# tvac_systems_interface.net
KiCad netlist of a schematic drawn in EAGLE
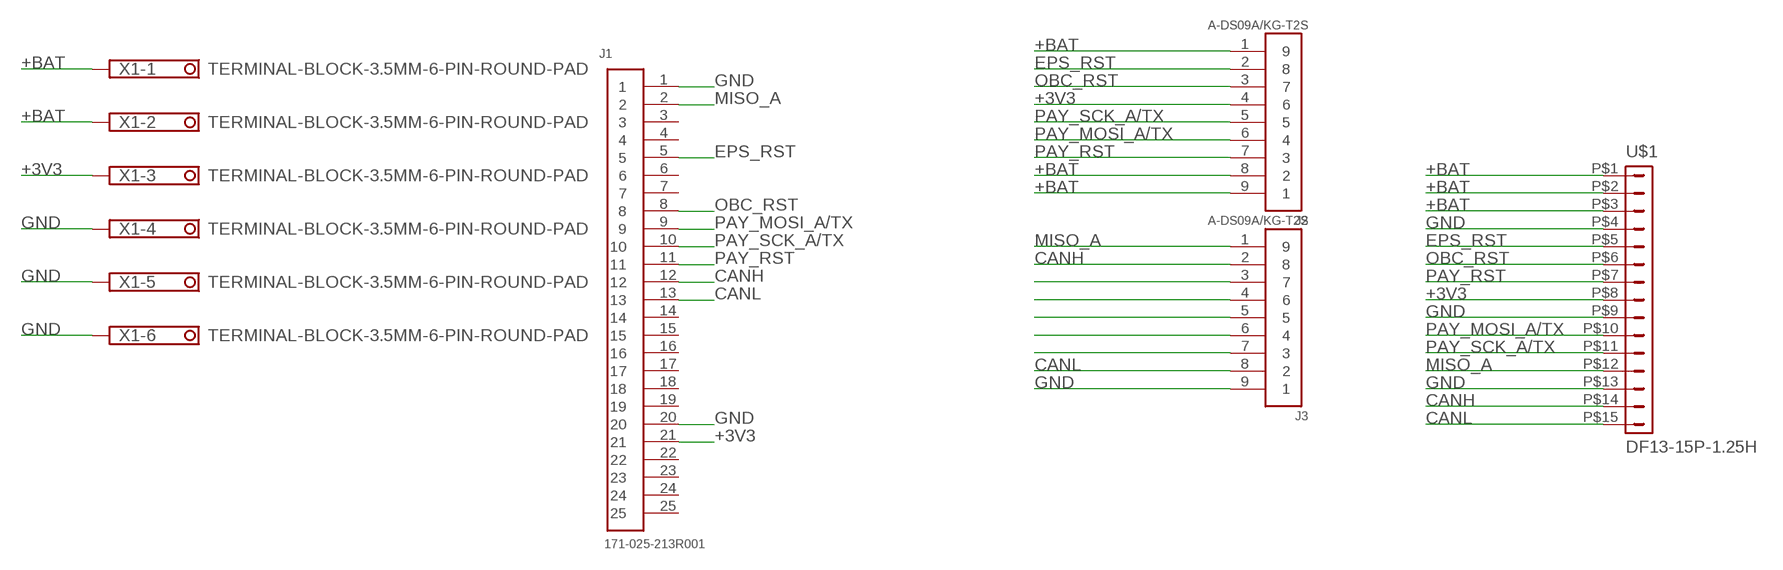
[diagram p0: schematic, sheet 1]

(export (version "E")
  (design (tool "Eeschema 10.0.6"))
  (components
    (comp (ref "J1")
      (value "171-025-213R001")
      (footprint "eagle-import:171-025-213R001")
      (fields
        (field (name "DIGIKEY_PART_NO") "4225FE-ND")
        (field (name "MANUFACTURER") "NorComp Inc.")
        (field (name "CREATED_BY") "PCBLayout.com")
      )
      (libsource (lib "eagle-import") (part "171-025-213R001"))
    )
    (comp (ref "J2")
      (value "A-DS09A/KG-T2S")
      (footprint "eagle-import:A-DS09A_KG-T2S")
      (fields
        (field (name "DIGI_KEY_PART_NUMBER") "AE10968-ND")
        (field (name "MANUFACTURER") "Assmann WSW Components")
        (field (name "MPN") "A-DS 09 A/KG-T2S")
        (field (name "CREATEDBY") "PCBLayout.com")
      )
      (libsource (lib "eagle-import") (part "A-DS09A/KG-T2S"))
    )
    (comp (ref "J3")
      (value "A-DS09A/KG-T2S")
      (footprint "eagle-import:A-DS09A_KG-T2S")
      (fields
        (field (name "DIGI_KEY_PART_NUMBER") "AE10968-ND")
        (field (name "MANUFACTURER") "Assmann WSW Components")
        (field (name "MPN") "A-DS 09 A/KG-T2S")
        (field (name "CREATEDBY") "PCBLayout.com")
      )
      (libsource (lib "eagle-import") (part "A-DS09A/KG-T2S"))
    )
    (comp (ref "U$1")
      (value "DF13-15P-1.25H")
      (footprint "eagle-import:DF13A-15P-1.25H")
      (libsource (lib "eagle-import") (part "DF13-15P-1.25H"))
    )
    (comp (ref "X1")
      (value "TERMINAL-BLOCK-3.5MM-6-PIN-ROUND-PAD")
      (footprint "eagle-import:TERMINAL-BLOCK-6-PIN-3.5MM-ROUND-PAD")
      (libsource (lib "eagle-import") (part "TERMINAL-BLOCK-3.5MM-6-PIN-ROUND-PAD"))
    )
  )
  (nets
    (net (code "1") (name "/+3V3") (class "Default")
      (node (ref "J1") (pin "21") (pinfunction "21_21") (pintype "passive"))
      (node (ref "J2") (pin "4") (pinfunction "6_4") (pintype "passive"))
      (node (ref "U$1") (pin "P$8") (pinfunction "8_P$8") (pintype "passive"))
      (node (ref "X1") (pin "3") (pinfunction "K_3") (pintype "passive"))
    )
    (net (code "2") (name "/+BAT") (class "Default")
      (node (ref "J2") (pin "1") (pinfunction "9_1") (pintype "passive"))
      (node (ref "J2") (pin "8") (pinfunction "2_8") (pintype "passive"))
      (node (ref "J2") (pin "9") (pinfunction "1_9") (pintype "passive"))
      (node (ref "U$1") (pin "P$1") (pinfunction "1_P$1") (pintype "passive"))
      (node (ref "U$1") (pin "P$2") (pinfunction "2_P$2") (pintype "passive"))
      (node (ref "U$1") (pin "P$3") (pinfunction "3_P$3") (pintype "passive"))
      (node (ref "X1") (pin "1") (pinfunction "K_1") (pintype "passive"))
      (node (ref "X1") (pin "2") (pinfunction "K_2") (pintype "passive"))
    )
    (net (code "3") (name "/CANH") (class "Default")
      (node (ref "J1") (pin "12") (pinfunction "12_12") (pintype "passive"))
      (node (ref "J3") (pin "2") (pinfunction "8_2") (pintype "passive"))
      (node (ref "U$1") (pin "P$14") (pinfunction "14_P$14") (pintype "passive"))
    )
    (net (code "4") (name "/CANL") (class "Default")
      (node (ref "J1") (pin "13") (pinfunction "13_13") (pintype "passive"))
      (node (ref "J3") (pin "8") (pinfunction "2_8") (pintype "passive"))
      (node (ref "U$1") (pin "P$15") (pinfunction "15_P$15") (pintype "passive"))
    )
    (net (code "5") (name "/EPS_RST") (class "Default")
      (node (ref "J1") (pin "5") (pinfunction "5_5") (pintype "passive"))
      (node (ref "J2") (pin "2") (pinfunction "8_2") (pintype "passive"))
      (node (ref "U$1") (pin "P$5") (pinfunction "5_P$5") (pintype "passive"))
    )
    (net (code "6") (name "/GND") (class "Default")
      (node (ref "J1") (pin "1") (pinfunction "1_1") (pintype "passive"))
      (node (ref "J1") (pin "20") (pinfunction "20_20") (pintype "passive"))
      (node (ref "J3") (pin "9") (pinfunction "1_9") (pintype "passive"))
      (node (ref "U$1") (pin "P$13") (pinfunction "13_P$13") (pintype "passive"))
      (node (ref "U$1") (pin "P$4") (pinfunction "4_P$4") (pintype "passive"))
      (node (ref "U$1") (pin "P$9") (pinfunction "9_P$9") (pintype "passive"))
      (node (ref "X1") (pin "4") (pinfunction "K_4") (pintype "passive"))
      (node (ref "X1") (pin "5") (pinfunction "K_5") (pintype "passive"))
      (node (ref "X1") (pin "6") (pinfunction "K_6") (pintype "passive"))
    )
    (net (code "7") (name "/MISO_A") (class "Default")
      (node (ref "J1") (pin "2") (pinfunction "2_2") (pintype "passive"))
      (node (ref "J3") (pin "1") (pinfunction "9_1") (pintype "passive"))
      (node (ref "U$1") (pin "P$12") (pinfunction "12_P$12") (pintype "passive"))
    )
    (net (code "8") (name "/OBC_RST") (class "Default")
      (node (ref "J1") (pin "8") (pinfunction "8_8") (pintype "passive"))
      (node (ref "J2") (pin "3") (pinfunction "7_3") (pintype "passive"))
      (node (ref "U$1") (pin "P$6") (pinfunction "6_P$6") (pintype "passive"))
    )
    (net (code "9") (name "/PAY_MOSI_A{slash}TX") (class "Default")
      (node (ref "J1") (pin "9") (pinfunction "9_9") (pintype "passive"))
      (node (ref "J2") (pin "6") (pinfunction "4_6") (pintype "passive"))
      (node (ref "U$1") (pin "P$10") (pinfunction "10_P$10") (pintype "passive"))
    )
    (net (code "10") (name "/PAY_RST") (class "Default")
      (node (ref "J1") (pin "11") (pinfunction "11_11") (pintype "passive"))
      (node (ref "J2") (pin "7") (pinfunction "3_7") (pintype "passive"))
      (node (ref "U$1") (pin "P$7") (pinfunction "7_P$7") (pintype "passive"))
    )
    (net (code "11") (name "/PAY_SCK_A{slash}TX") (class "Default")
      (node (ref "J1") (pin "10") (pinfunction "10_10") (pintype "passive"))
      (node (ref "J2") (pin "5") (pinfunction "5_5") (pintype "passive"))
      (node (ref "U$1") (pin "P$11") (pinfunction "11_P$11") (pintype "passive"))
    )
    (net (code "12") (name "unconnected-(J1-Pad3)") (class "Default")
      (node (ref "J1") (pin "3") (pinfunction "3_3") (pintype "passive"))
    )
    (net (code "13") (name "unconnected-(J1-Pad4)") (class "Default")
      (node (ref "J1") (pin "4") (pinfunction "4_4") (pintype "passive"))
    )
    (net (code "14") (name "unconnected-(J1-Pad6)") (class "Default")
      (node (ref "J1") (pin "6") (pinfunction "6_6") (pintype "passive"))
    )
    (net (code "15") (name "unconnected-(J1-Pad7)") (class "Default")
      (node (ref "J1") (pin "7") (pinfunction "7_7") (pintype "passive"))
    )
    (net (code "16") (name "unconnected-(J1-Pad14)") (class "Default")
      (node (ref "J1") (pin "14") (pinfunction "14_14") (pintype "passive"))
    )
    (net (code "17") (name "unconnected-(J1-Pad15)") (class "Default")
      (node (ref "J1") (pin "15") (pinfunction "15_15") (pintype "passive"))
    )
    (net (code "18") (name "unconnected-(J1-Pad16)") (class "Default")
      (node (ref "J1") (pin "16") (pinfunction "16_16") (pintype "passive"))
    )
    (net (code "19") (name "unconnected-(J1-Pad17)") (class "Default")
      (node (ref "J1") (pin "17") (pinfunction "17_17") (pintype "passive"))
    )
    (net (code "20") (name "unconnected-(J1-Pad18)") (class "Default")
      (node (ref "J1") (pin "18") (pinfunction "18_18") (pintype "passive"))
    )
    (net (code "21") (name "unconnected-(J1-Pad19)") (class "Default")
      (node (ref "J1") (pin "19") (pinfunction "19_19") (pintype "passive"))
    )
    (net (code "22") (name "unconnected-(J1-Pad22)") (class "Default")
      (node (ref "J1") (pin "22") (pinfunction "22_22") (pintype "passive"))
    )
    (net (code "23") (name "unconnected-(J1-Pad23)") (class "Default")
      (node (ref "J1") (pin "23") (pinfunction "23_23") (pintype "passive"))
    )
    (net (code "24") (name "unconnected-(J1-Pad24)") (class "Default")
      (node (ref "J1") (pin "24") (pinfunction "24_24") (pintype "passive"))
    )
    (net (code "25") (name "unconnected-(J1-Pad25)") (class "Default")
      (node (ref "J1") (pin "25") (pinfunction "25_25") (pintype "passive"))
    )
    (net (code "26") (name "unconnected-(J3-3-Pad7)") (class "Default")
      (node (ref "J3") (pin "7") (pinfunction "3_7") (pintype "passive"))
    )
    (net (code "27") (name "unconnected-(J3-4-Pad6)") (class "Default")
      (node (ref "J3") (pin "6") (pinfunction "4_6") (pintype "passive"))
    )
    (net (code "28") (name "unconnected-(J3-6-Pad4)") (class "Default")
      (node (ref "J3") (pin "4") (pinfunction "6_4") (pintype "passive"))
    )
    (net (code "29") (name "unconnected-(J3-7-Pad3)") (class "Default")
      (node (ref "J3") (pin "3") (pinfunction "7_3") (pintype "passive"))
    )
    (net (code "30") (name "unconnected-(J3-Pad5)") (class "Default")
      (node (ref "J3") (pin "5") (pinfunction "5_5") (pintype "passive"))
    )
  )
)
